# Sch2ByteChannel.net
KiCad netlist of a schematic drawn in Altium Designer
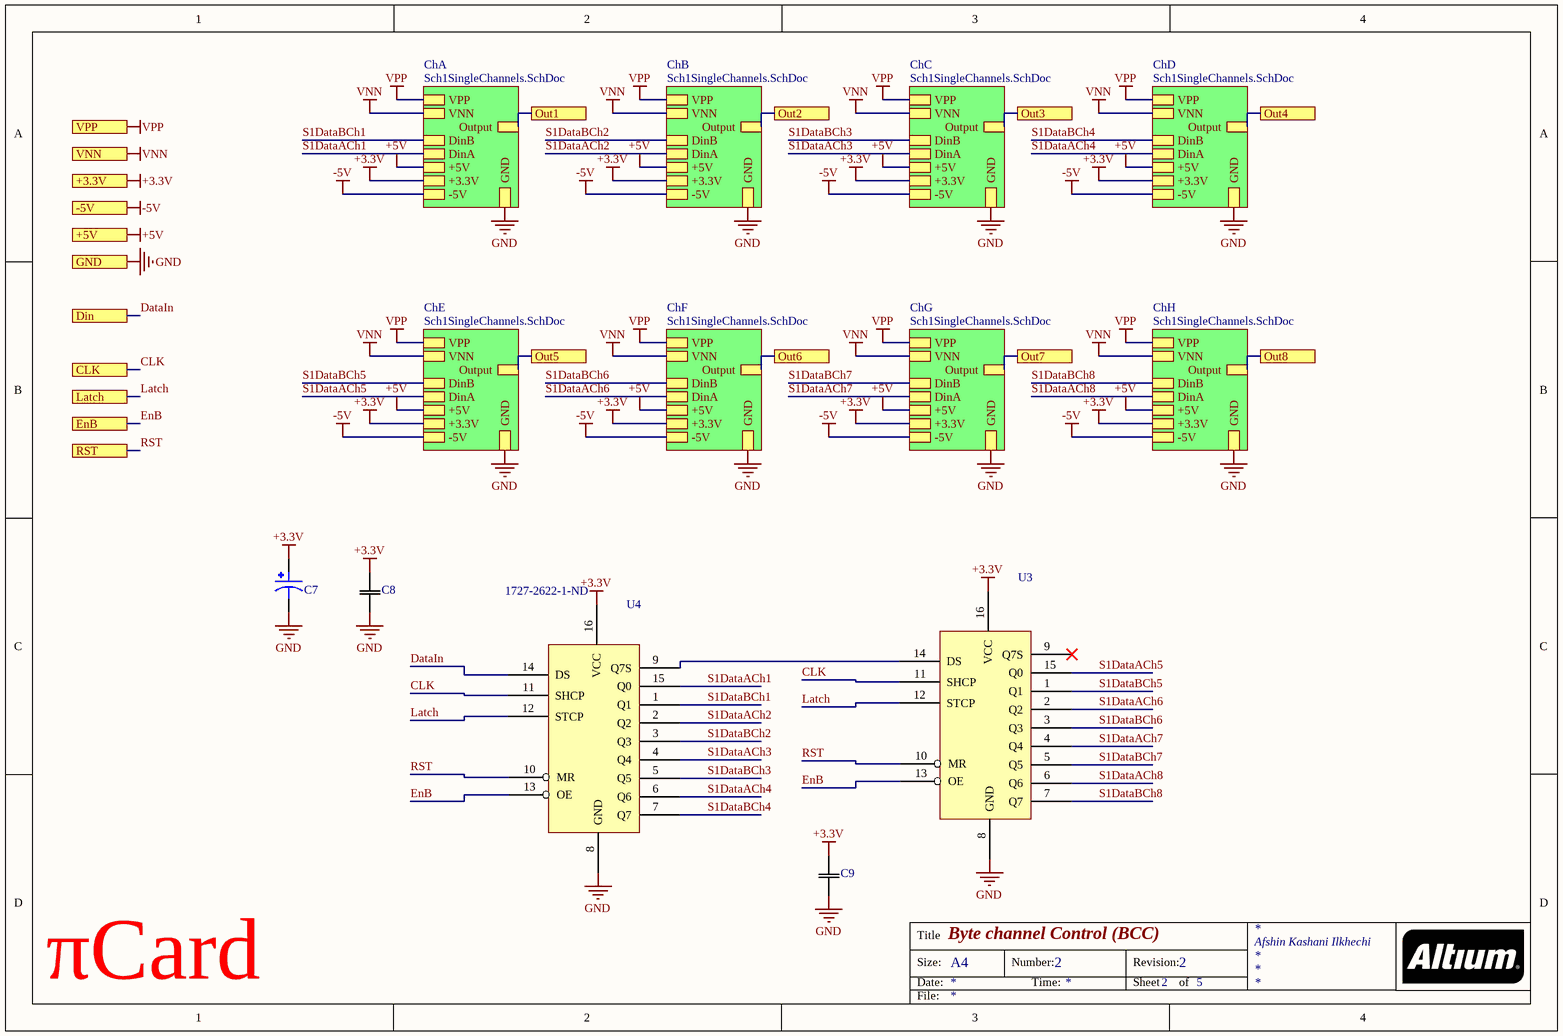
[diagram p0: Sch2ByteChannel.SchDoc]

(export (version "E")
  (design (tool "Eeschema 10.0.6"))
  (components
    (comp (ref "C7")
      (value "T55A107M6R3C0200")
      (footprint "C1206")
      (description "Tantalium")
      (libsource (lib "Afshin Library") (part "Cap_1206"))
    )
    (comp (ref "C8")
      (value "C0805C104Z5VACTU")
      (footprint "C0805")
      (libsource (lib "Afshin Library") (part "Cap_0805"))
    )
    (comp (ref "C9")
      (value "C0805C104Z5VACTU")
      (footprint "C0805")
      (libsource (lib "Afshin Library") (part "Cap_0805"))
    )
    (comp (ref "U3")
      (value "74HC595BQ-Q100,115")
      (footprint "QFN50P250X350X100-17N")
      (libsource (lib "Afshin Library") (part "74HC595BQ-Q100,115"))
    )
    (comp (ref "U4")
      (value "74HC595BQ-Q100,115")
      (footprint "QFN50P250X350X100-17N")
      (fields (field (name "SUPPLIER PART NUMBER 1") "1727-2622-1-ND"))
      (libsource (lib "Afshin Library") (part "74HC595BQ-Q100,115"))
    )
  )
  (nets
    (net (code "1") (name "+3.3V") (class "Default")
      (node (ref "C7") (pin "1") (pinfunction "POS_1") (pintype "passive"))
      (node (ref "C8") (pin "2") (pinfunction "2_2") (pintype "passive"))
      (node (ref "C9") (pin "2") (pinfunction "2_2") (pintype "passive"))
      (node (ref "U3") (pin "16") (pinfunction "VCC_16") (pintype "passive"))
      (node (ref "U4") (pin "16") (pinfunction "VCC_16") (pintype "passive"))
    )
    (net (code "4") (name "/CLK") (class "Default")
      (node (ref "U3") (pin "11") (pinfunction "SHCP_11") (pintype "passive"))
      (node (ref "U4") (pin "11") (pinfunction "SHCP_11") (pintype "passive"))
    )
    (net (code "5") (name "/DataIn") (class "Default")
      (node (ref "U4") (pin "14") (pinfunction "DS_14") (pintype "passive"))
    )
    (net (code "6") (name "/EnB") (class "Default")
      (node (ref "U3") (pin "13") (pinfunction "OE_13") (pintype "passive"))
      (node (ref "U4") (pin "13") (pinfunction "OE_13") (pintype "passive"))
    )
    (net (code "7") (name "/Latch") (class "Default")
      (node (ref "U3") (pin "12") (pinfunction "STCP_12") (pintype "passive"))
      (node (ref "U4") (pin "12") (pinfunction "STCP_12") (pintype "passive"))
    )
    (net (code "16") (name "/RST") (class "Default")
      (node (ref "U3") (pin "10") (pinfunction "MR_10") (pintype "passive"))
      (node (ref "U4") (pin "10") (pinfunction "MR_10") (pintype "passive"))
    )
    (net (code "17") (name "/S1DataACh1") (class "Default")
      (node (ref "U4") (pin "15") (pinfunction "Q0_15") (pintype "passive"))
    )
    (net (code "18") (name "/S1DataACh2") (class "Default")
      (node (ref "U4") (pin "2") (pinfunction "Q2_2") (pintype "passive"))
    )
    (net (code "19") (name "/S1DataACh3") (class "Default")
      (node (ref "U4") (pin "4") (pinfunction "Q4_4") (pintype "passive"))
    )
    (net (code "20") (name "/S1DataACh4") (class "Default")
      (node (ref "U4") (pin "6") (pinfunction "Q6_6") (pintype "passive"))
    )
    (net (code "21") (name "/S1DataACh5") (class "Default")
      (node (ref "U3") (pin "15") (pinfunction "Q0_15") (pintype "passive"))
    )
    (net (code "22") (name "/S1DataACh6") (class "Default")
      (node (ref "U3") (pin "2") (pinfunction "Q2_2") (pintype "passive"))
    )
    (net (code "23") (name "/S1DataACh7") (class "Default")
      (node (ref "U3") (pin "4") (pinfunction "Q4_4") (pintype "passive"))
    )
    (net (code "24") (name "/S1DataACh8") (class "Default")
      (node (ref "U3") (pin "6") (pinfunction "Q6_6") (pintype "passive"))
    )
    (net (code "25") (name "/S1DataBCh1") (class "Default")
      (node (ref "U4") (pin "1") (pinfunction "Q1_1") (pintype "passive"))
    )
    (net (code "26") (name "/S1DataBCh2") (class "Default")
      (node (ref "U4") (pin "3") (pinfunction "Q3_3") (pintype "passive"))
    )
    (net (code "27") (name "/S1DataBCh3") (class "Default")
      (node (ref "U4") (pin "5") (pinfunction "Q5_5") (pintype "passive"))
    )
    (net (code "28") (name "/S1DataBCh4") (class "Default")
      (node (ref "U4") (pin "7") (pinfunction "Q7_7") (pintype "passive"))
    )
    (net (code "29") (name "/S1DataBCh5") (class "Default")
      (node (ref "U3") (pin "1") (pinfunction "Q1_1") (pintype "passive"))
    )
    (net (code "30") (name "/S1DataBCh6") (class "Default")
      (node (ref "U3") (pin "3") (pinfunction "Q3_3") (pintype "passive"))
    )
    (net (code "31") (name "/S1DataBCh7") (class "Default")
      (node (ref "U3") (pin "5") (pinfunction "Q5_5") (pintype "passive"))
    )
    (net (code "32") (name "/S1DataBCh8") (class "Default")
      (node (ref "U3") (pin "7") (pinfunction "Q7_7") (pintype "passive"))
    )
    (net (code "33") (name "GND") (class "Default")
      (node (ref "C7") (pin "2") (pinfunction "NEG_2") (pintype "passive"))
      (node (ref "C8") (pin "1") (pinfunction "1_1") (pintype "passive"))
      (node (ref "C9") (pin "1") (pinfunction "1_1") (pintype "passive"))
      (node (ref "U3") (pin "8") (pinfunction "GND_8") (pintype "passive"))
      (node (ref "U4") (pin "8") (pinfunction "GND_8") (pintype "passive"))
    )
    (net (code "34") (name "Net-(U3-DS)") (class "Default")
      (node (ref "U3") (pin "14") (pinfunction "DS_14") (pintype "passive"))
      (node (ref "U4") (pin "9") (pinfunction "Q7S_9") (pintype "passive"))
    )
    (net (code "37") (name "unconnected-(U3-Q7S-Pad9)") (class "Default")
      (node (ref "U3") (pin "9") (pinfunction "Q7S_9") (pintype "passive+no_connect"))
    )
  )
)
